# RocketSense.net
KiCad netlist of a schematic drawn in EAGLE
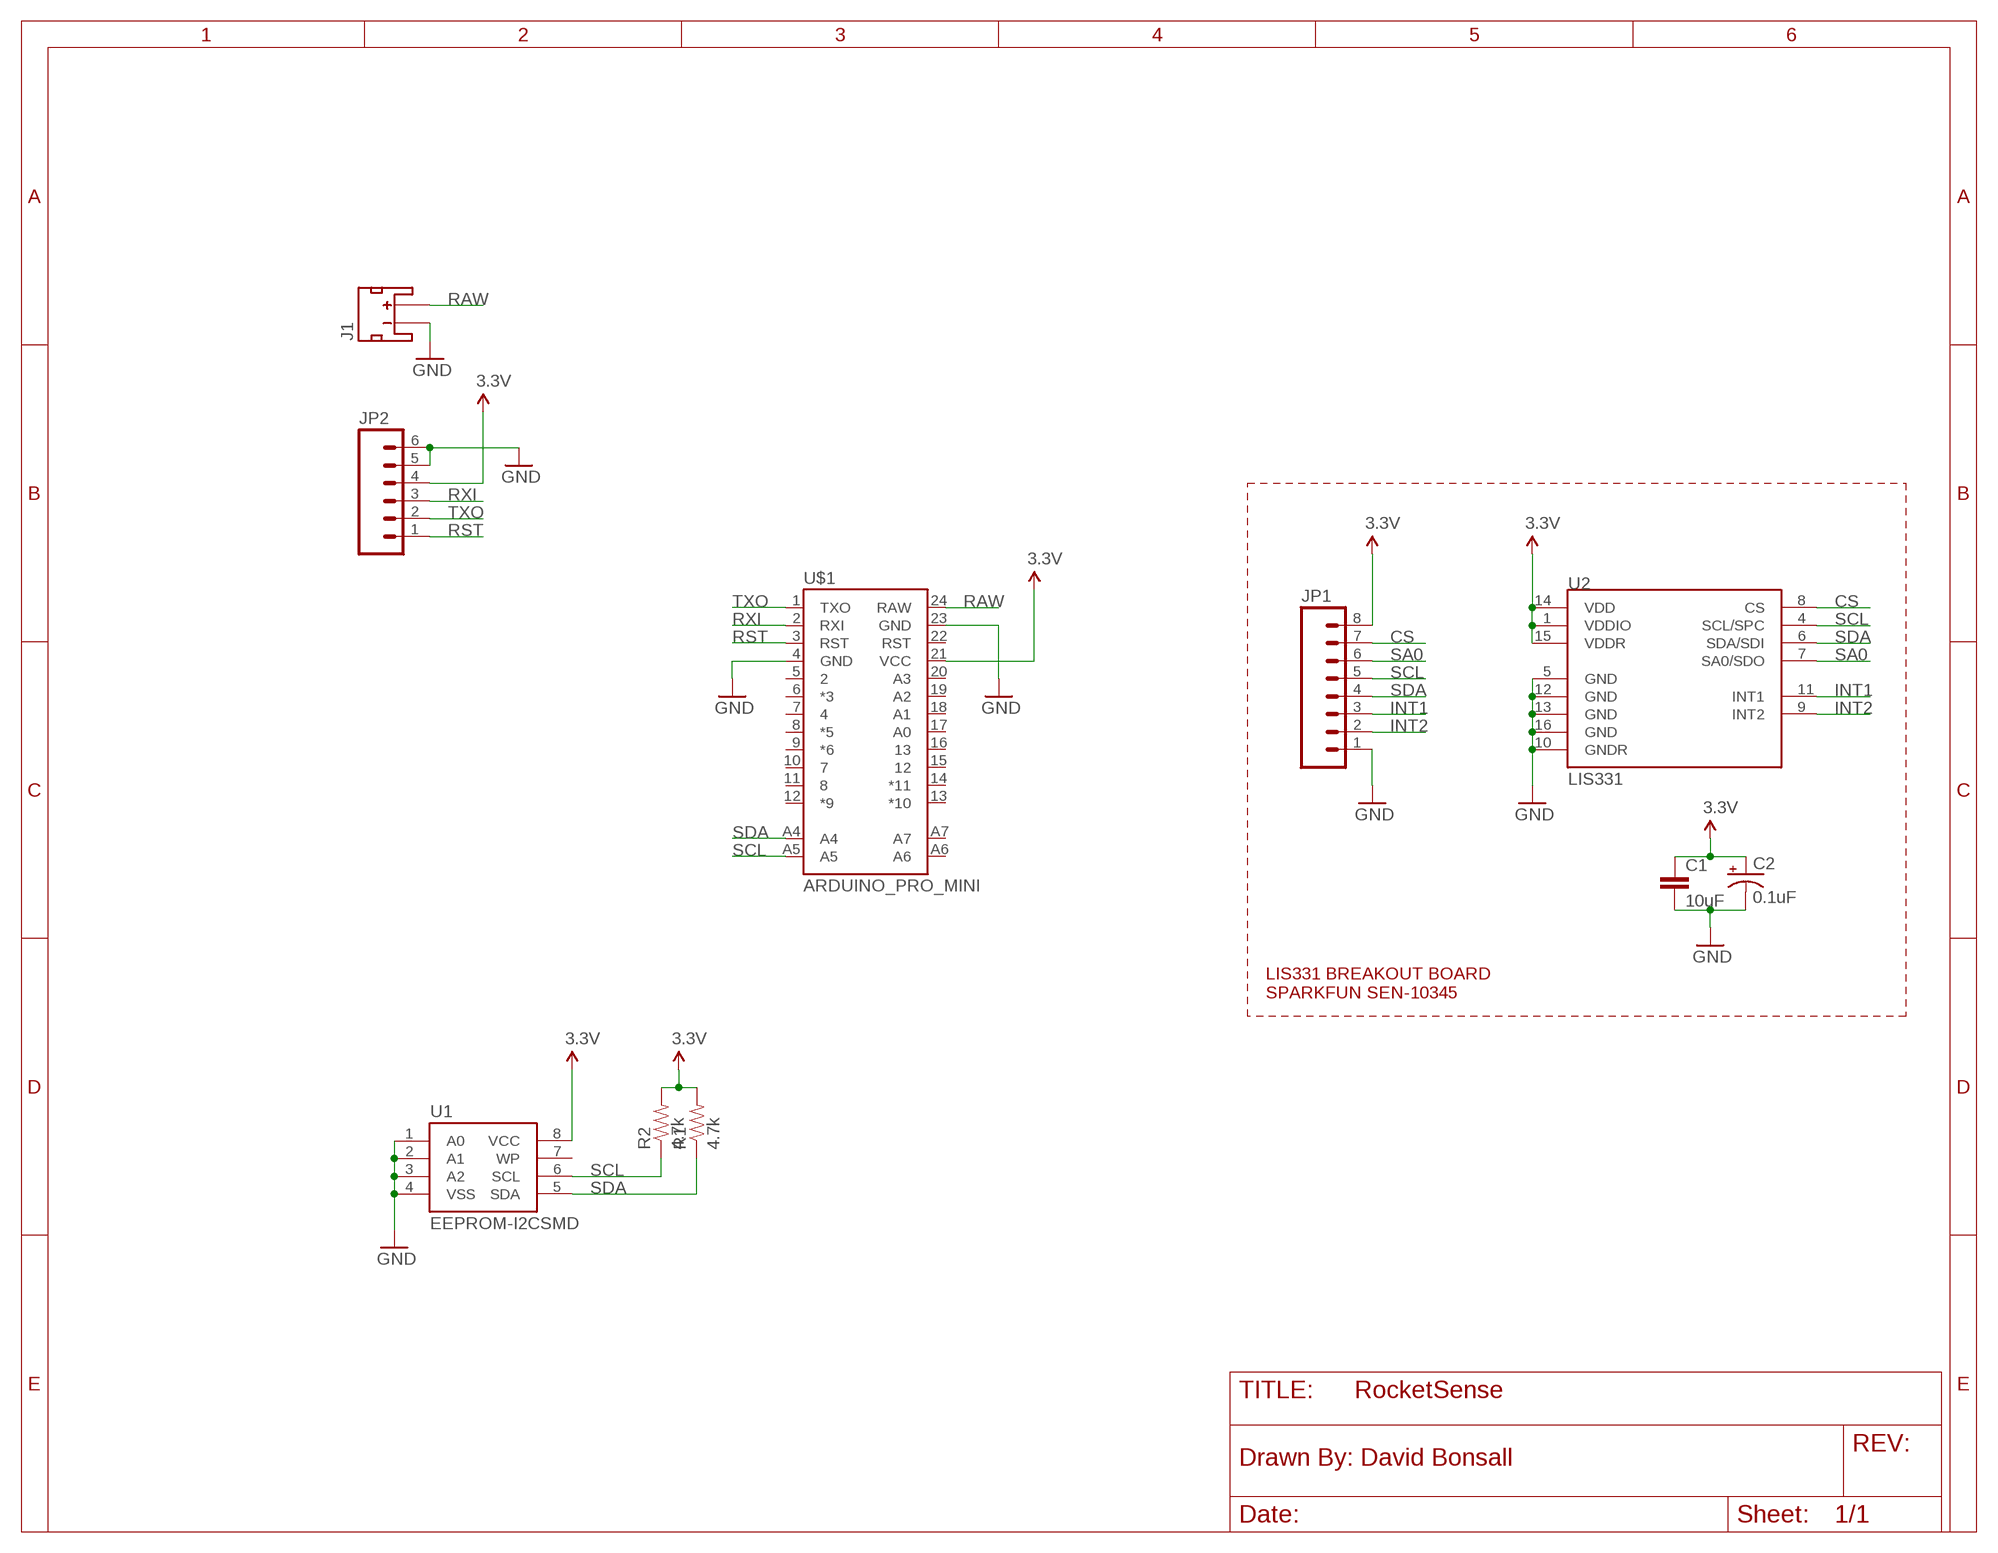
[diagram p0: schematic, sheet 1]

(export (version "E")
  (design (tool "Eeschema 10.0.6"))
  (components
    (comp (ref "C1")
      (value "10uF")
      (footprint "eagle-import:0402-CAP")
      (libsource (lib "eagle-import") (part "CAP0402-CAP"))
    )
    (comp (ref "C2")
      (value "0.1uF")
      (footprint "eagle-import:EIA3216")
      (libsource (lib "eagle-import") (part "CAP_POL1206"))
    )
    (comp (ref "J1")
      (value "JST_2MM_MALE")
      (footprint "eagle-import:JST-2-SMD")
      (libsource (lib "eagle-import") (part "JST_2MM_MALE"))
    )
    (comp (ref "JP1")
      (value "M08")
      (footprint "eagle-import:1X08_PIN1_NO_SILK")
      (libsource (lib "eagle-import") (part "M08"))
    )
    (comp (ref "JP2")
      (value "M06SIP")
      (footprint "eagle-import:1X06")
      (libsource (lib "eagle-import") (part "M06SIP"))
    )
    (comp (ref "R1")
      (value "4.7k")
      (footprint "eagle-import:1_6W-RES")
      (libsource (lib "eagle-import") (part "RESISTORPTH-1/6W"))
    )
    (comp (ref "R2")
      (value "4.7k")
      (footprint "eagle-import:1_6W-RES")
      (libsource (lib "eagle-import") (part "RESISTORPTH-1/6W"))
    )
    (comp (ref "U$1")
      (value "ARDUINO_PRO_MINI")
      (footprint "eagle-import:ARDUINO_PRO_MINI")
      (libsource (lib "eagle-import") (part "ARDUINO_PRO_MINI"))
    )
    (comp (ref "U1")
      (value "EEPROM-I2CSMD")
      (footprint "eagle-import:SO08")
      (libsource (lib "eagle-import") (part "EEPROM-I2CSMD"))
    )
    (comp (ref "U2")
      (value "LIS331")
      (footprint "eagle-import:LGA16-3MM")
      (libsource (lib "eagle-import") (part "LIS331"))
    )
  )
  (nets
    (net (code "1") (name "/CS") (class "Default")
      (node (ref "JP1") (pin "7") (pinfunction "7_7") (pintype "passive"))
      (node (ref "U2") (pin "8") (pinfunction "CS_8") (pintype "bidirectional"))
    )
    (net (code "2") (name "/INT1") (class "Default")
      (node (ref "JP1") (pin "3") (pinfunction "3_3") (pintype "passive"))
      (node (ref "U2") (pin "11") (pinfunction "INT1_11") (pintype "bidirectional"))
    )
    (net (code "3") (name "/INT2") (class "Default")
      (node (ref "JP1") (pin "2") (pinfunction "2_2") (pintype "passive"))
      (node (ref "U2") (pin "9") (pinfunction "INT2_9") (pintype "bidirectional"))
    )
    (net (code "4") (name "/RAW") (class "Default")
      (node (ref "J1") (pin "2") (pinfunction "+_2") (pintype "bidirectional"))
      (node (ref "U$1") (pin "24") (pinfunction "RAW_24") (pintype "bidirectional"))
    )
    (net (code "5") (name "/RST") (class "Default")
      (node (ref "JP2") (pin "1") (pinfunction "1_1") (pintype "passive"))
      (node (ref "U$1") (pin "3") (pinfunction "RST_3") (pintype "bidirectional"))
    )
    (net (code "6") (name "/RXI") (class "Default")
      (node (ref "JP2") (pin "3") (pinfunction "3_3") (pintype "passive"))
      (node (ref "U$1") (pin "2") (pinfunction "RXI_2") (pintype "bidirectional"))
    )
    (net (code "7") (name "/SA0") (class "Default")
      (node (ref "JP1") (pin "6") (pinfunction "6_6") (pintype "passive"))
      (node (ref "U2") (pin "7") (pinfunction "SA0/SDO_7") (pintype "bidirectional"))
    )
    (net (code "8") (name "/SCL") (class "Default")
      (node (ref "JP1") (pin "5") (pinfunction "5_5") (pintype "passive"))
      (node (ref "R2") (pin "1") (pinfunction "1_1") (pintype "passive"))
      (node (ref "U$1") (pin "A5") (pinfunction "A5_A5") (pintype "bidirectional"))
      (node (ref "U1") (pin "6") (pinfunction "SCL_6") (pintype "bidirectional"))
      (node (ref "U2") (pin "4") (pinfunction "SCL/SPC_4") (pintype "bidirectional"))
    )
    (net (code "9") (name "/SDA") (class "Default")
      (node (ref "JP1") (pin "4") (pinfunction "4_4") (pintype "passive"))
      (node (ref "R1") (pin "1") (pinfunction "1_1") (pintype "passive"))
      (node (ref "U$1") (pin "A4") (pinfunction "A4_A4") (pintype "bidirectional"))
      (node (ref "U1") (pin "5") (pinfunction "SDA_5") (pintype "bidirectional"))
      (node (ref "U2") (pin "6") (pinfunction "SDA/SDI_6") (pintype "bidirectional"))
    )
    (net (code "10") (name "/TXO") (class "Default")
      (node (ref "JP2") (pin "2") (pinfunction "2_2") (pintype "passive"))
      (node (ref "U$1") (pin "1") (pinfunction "TXO_1") (pintype "bidirectional"))
    )
    (net (code "11") (name "3.3V") (class "Default")
      (node (ref "C1") (pin "1") (pinfunction "1_1") (pintype "passive"))
      (node (ref "C2") (pin "A") (pinfunction "+_A") (pintype "passive"))
      (node (ref "JP1") (pin "8") (pinfunction "8_8") (pintype "passive"))
      (node (ref "JP2") (pin "4") (pinfunction "4_4") (pintype "passive"))
      (node (ref "R1") (pin "2") (pinfunction "2_2") (pintype "passive"))
      (node (ref "R2") (pin "2") (pinfunction "2_2") (pintype "passive"))
      (node (ref "U$1") (pin "21") (pinfunction "VCC_21") (pintype "bidirectional"))
      (node (ref "U1") (pin "8") (pinfunction "VCC_8") (pintype "power_in"))
      (node (ref "U2") (pin "1") (pinfunction "VDDIO_1") (pintype "bidirectional"))
      (node (ref "U2") (pin "14") (pinfunction "VDD_14") (pintype "bidirectional"))
      (node (ref "U2") (pin "15") (pinfunction "VDDR_15") (pintype "bidirectional"))
    )
    (net (code "12") (name "GND") (class "Default")
      (node (ref "C1") (pin "2") (pinfunction "2_2") (pintype "passive"))
      (node (ref "C2") (pin "C") (pinfunction "-_C") (pintype "passive"))
      (node (ref "J1") (pin "1") (pinfunction "-_1") (pintype "bidirectional"))
      (node (ref "JP1") (pin "1") (pinfunction "1_1") (pintype "passive"))
      (node (ref "JP2") (pin "5") (pinfunction "5_5") (pintype "passive"))
      (node (ref "JP2") (pin "6") (pinfunction "6_6") (pintype "passive"))
      (node (ref "U$1") (pin "23") (pinfunction "GND_23") (pintype "bidirectional"))
      (node (ref "U$1") (pin "4") (pinfunction "GND_4") (pintype "bidirectional"))
      (node (ref "U1") (pin "1") (pinfunction "A0_1") (pintype "bidirectional"))
      (node (ref "U1") (pin "2") (pinfunction "A1_2") (pintype "bidirectional"))
      (node (ref "U1") (pin "3") (pinfunction "A2_3") (pintype "bidirectional"))
      (node (ref "U1") (pin "4") (pinfunction "VSS_4") (pintype "power_in"))
      (node (ref "U2") (pin "10") (pinfunction "GNDR_10") (pintype "bidirectional"))
      (node (ref "U2") (pin "12") (pinfunction "GND_12") (pintype "bidirectional"))
      (node (ref "U2") (pin "13") (pinfunction "GND_13") (pintype "bidirectional"))
      (node (ref "U2") (pin "16") (pinfunction "GND_16") (pintype "bidirectional"))
      (node (ref "U2") (pin "5") (pinfunction "GND_5") (pintype "bidirectional"))
    )
    (net (code "13") (name "unconnected-(J1-PAD1-PadNC1)") (class "Default")
      (node (ref "J1") (pin "NC1") (pinfunction "PAD1_NC1") (pintype "bidirectional"))
    )
    (net (code "14") (name "unconnected-(J1-PAD2-PadNC2)") (class "Default")
      (node (ref "J1") (pin "NC2") (pinfunction "PAD2_NC2") (pintype "bidirectional"))
    )
    (net (code "15") (name "unconnected-(U$1-*3-Pad6)") (class "Default")
      (node (ref "U$1") (pin "6") (pinfunction "*3_6") (pintype "bidirectional"))
    )
    (net (code "16") (name "unconnected-(U$1-*5-Pad8)") (class "Default")
      (node (ref "U$1") (pin "8") (pinfunction "*5_8") (pintype "bidirectional"))
    )
    (net (code "17") (name "unconnected-(U$1-*6-Pad9)") (class "Default")
      (node (ref "U$1") (pin "9") (pinfunction "*6_9") (pintype "bidirectional"))
    )
    (net (code "18") (name "unconnected-(U$1-*9-Pad12)") (class "Default")
      (node (ref "U$1") (pin "12") (pinfunction "*9_12") (pintype "bidirectional"))
    )
    (net (code "19") (name "unconnected-(U$1-*10-Pad13)") (class "Default")
      (node (ref "U$1") (pin "13") (pinfunction "*10_13") (pintype "bidirectional"))
    )
    (net (code "20") (name "unconnected-(U$1-*11-Pad14)") (class "Default")
      (node (ref "U$1") (pin "14") (pinfunction "*11_14") (pintype "bidirectional"))
    )
    (net (code "21") (name "unconnected-(U$1-2-Pad5)") (class "Default")
      (node (ref "U$1") (pin "5") (pinfunction "2_5") (pintype "bidirectional"))
    )
    (net (code "22") (name "unconnected-(U$1-4-Pad7)") (class "Default")
      (node (ref "U$1") (pin "7") (pinfunction "4_7") (pintype "bidirectional"))
    )
    (net (code "23") (name "unconnected-(U$1-7-Pad10)") (class "Default")
      (node (ref "U$1") (pin "10") (pinfunction "7_10") (pintype "bidirectional"))
    )
    (net (code "24") (name "unconnected-(U$1-8-Pad11)") (class "Default")
      (node (ref "U$1") (pin "11") (pinfunction "8_11") (pintype "bidirectional"))
    )
    (net (code "25") (name "unconnected-(U$1-12-Pad15)") (class "Default")
      (node (ref "U$1") (pin "15") (pinfunction "12_15") (pintype "bidirectional"))
    )
    (net (code "26") (name "unconnected-(U$1-13-Pad16)") (class "Default")
      (node (ref "U$1") (pin "16") (pinfunction "13_16") (pintype "bidirectional"))
    )
    (net (code "27") (name "unconnected-(U$1-A0-Pad17)") (class "Default")
      (node (ref "U$1") (pin "17") (pinfunction "A0_17") (pintype "bidirectional"))
    )
    (net (code "28") (name "unconnected-(U$1-A1-Pad18)") (class "Default")
      (node (ref "U$1") (pin "18") (pinfunction "A1_18") (pintype "bidirectional"))
    )
    (net (code "29") (name "unconnected-(U$1-A2-Pad19)") (class "Default")
      (node (ref "U$1") (pin "19") (pinfunction "A2_19") (pintype "bidirectional"))
    )
    (net (code "30") (name "unconnected-(U$1-A3-Pad20)") (class "Default")
      (node (ref "U$1") (pin "20") (pinfunction "A3_20") (pintype "bidirectional"))
    )
    (net (code "31") (name "unconnected-(U$1-PadA6)") (class "Default")
      (node (ref "U$1") (pin "A6") (pinfunction "A6_A6") (pintype "bidirectional"))
    )
    (net (code "32") (name "unconnected-(U$1-PadA7)") (class "Default")
      (node (ref "U$1") (pin "A7") (pinfunction "A7_A7") (pintype "bidirectional"))
    )
    (net (code "33") (name "unconnected-(U$1-RST-Pad22)") (class "Default")
      (node (ref "U$1") (pin "22") (pinfunction "RST_22") (pintype "bidirectional"))
    )
    (net (code "34") (name "unconnected-(U1-WP-Pad7)") (class "Default")
      (node (ref "U1") (pin "7") (pinfunction "WP_7") (pintype "bidirectional"))
    )
  )
)
